# USBTINYISP.net
KiCad netlist of a schematic drawn in EAGLE
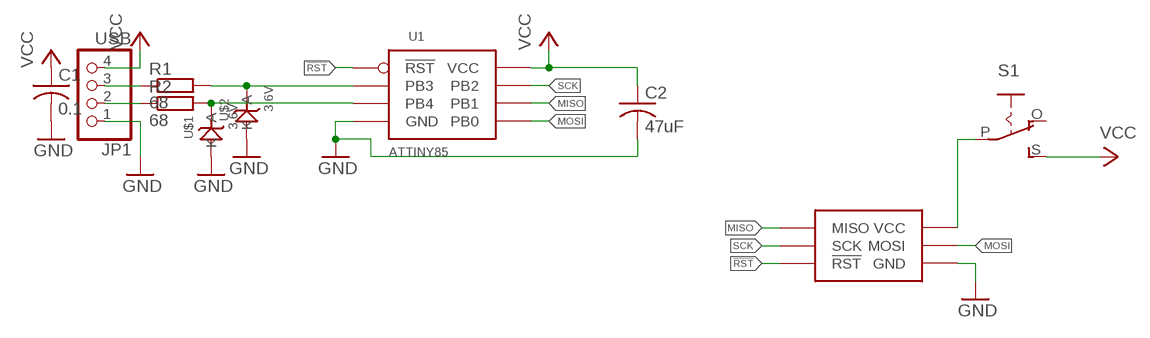
[diagram p0: schematic, sheet 1]

(export (version "E")
  (design (tool "Eeschema 10.0.6"))
  (components
    (comp (ref "C1")
      (value "0.1")
      (footprint "eagle-import:C025-025X050")
      (libsource (lib "eagle-import") (part "C-US025-025X050"))
    )
    (comp (ref "C2")
      (value "47uF")
      (footprint "eagle-import:C025-025X050")
      (libsource (lib "eagle-import") (part "C-US025-025X050"))
    )
    (comp (ref "ICSP1")
      (value "AVRISCP")
      (footprint "eagle-import:AVRICSP")
      (libsource (lib "eagle-import") (part "AVRISCP"))
    )
    (comp (ref "JP1")
      (value "USB")
      (footprint "eagle-import:1X04")
      (libsource (lib "eagle-import") (part "PINHD-1X4"))
    )
    (comp (ref "R1")
      (value "68")
      (footprint "eagle-import:0207_7")
      (libsource (lib "eagle-import") (part "R-EU_0207/7"))
    )
    (comp (ref "R2")
      (value "68")
      (footprint "eagle-import:0207_7")
      (libsource (lib "eagle-import") (part "R-EU_0207/7"))
    )
    (comp (ref "S1")
      (value "EG1218S")
      (footprint "eagle-import:EG1218")
      (libsource (lib "eagle-import") (part "EG1218S"))
    )
    (comp (ref "U$1")
      (value "3.6V")
      (footprint "eagle-import:Z3V6")
      (libsource (lib "eagle-import") (part "Z3V6"))
    )
    (comp (ref "U$2")
      (value "3.6V")
      (footprint "eagle-import:Z3V6")
      (libsource (lib "eagle-import") (part "Z3V6"))
    )
    (comp (ref "U1")
      (value "ATTINY85")
      (footprint "eagle-import:DIP8")
      (libsource (lib "eagle-import") (part "ATTINY85"))
    )
  )
  (nets
    (net (code "1") (name "/~{RST}") (class "Default")
      (node (ref "ICSP1") (pin "P$5") (pinfunction "~{RST}_P$5") (pintype "bidirectional"))
      (node (ref "U1") (pin "P$1") (pinfunction "~{RST}_P$1") (pintype "bidirectional"))
    )
    (net (code "2") (name "GND") (class "Default")
      (node (ref "C1") (pin "2") (pinfunction "2_2") (pintype "passive"))
      (node (ref "C2") (pin "2") (pinfunction "2_2") (pintype "passive"))
      (node (ref "ICSP1") (pin "P$6") (pinfunction "GND_P$6") (pintype "power_in"))
      (node (ref "JP1") (pin "1") (pinfunction "1_1") (pintype "passive"))
      (node (ref "U$1") (pin "P$2") (pinfunction "A_P$2") (pintype "power_in"))
      (node (ref "U$2") (pin "P$2") (pinfunction "A_P$2") (pintype "power_in"))
      (node (ref "U1") (pin "P$4") (pinfunction "GND_P$4") (pintype "power_in"))
    )
    (net (code "3") (name "MISO") (class "Default")
      (node (ref "ICSP1") (pin "P$1") (pinfunction "MISO_P$1") (pintype "bidirectional"))
      (node (ref "U1") (pin "P$6") (pinfunction "PB1_P$6") (pintype "bidirectional"))
    )
    (net (code "4") (name "MOSI") (class "Default")
      (node (ref "ICSP1") (pin "P$4") (pinfunction "MOSI_P$4") (pintype "bidirectional"))
      (node (ref "U1") (pin "P$5") (pinfunction "PB0_P$5") (pintype "bidirectional"))
    )
    (net (code "5") (name "Net-(ICSP1-VCC)") (class "Default")
      (node (ref "ICSP1") (pin "P$2") (pinfunction "VCC_P$2") (pintype "power_in"))
      (node (ref "S1") (pin "P") (pinfunction "P_P") (pintype "passive"))
    )
    (net (code "6") (name "Net-(JP1-Pad2)") (class "Default")
      (node (ref "JP1") (pin "2") (pinfunction "2_2") (pintype "passive"))
      (node (ref "R2") (pin "1") (pinfunction "1_1") (pintype "passive"))
    )
    (net (code "7") (name "Net-(JP1-Pad3)") (class "Default")
      (node (ref "JP1") (pin "3") (pinfunction "3_3") (pintype "passive"))
      (node (ref "R1") (pin "1") (pinfunction "1_1") (pintype "passive"))
    )
    (net (code "8") (name "Net-(U$1-K)") (class "Default")
      (node (ref "R2") (pin "2") (pinfunction "2_2") (pintype "passive"))
      (node (ref "U$1") (pin "P$1") (pinfunction "K_P$1") (pintype "power_in"))
      (node (ref "U1") (pin "P$3") (pinfunction "PB4_P$3") (pintype "bidirectional"))
    )
    (net (code "9") (name "Net-(U$2-K)") (class "Default")
      (node (ref "R1") (pin "2") (pinfunction "2_2") (pintype "passive"))
      (node (ref "U$2") (pin "P$1") (pinfunction "K_P$1") (pintype "power_in"))
      (node (ref "U1") (pin "P$2") (pinfunction "PB3_P$2") (pintype "bidirectional"))
    )
    (net (code "10") (name "SCK") (class "Default")
      (node (ref "ICSP1") (pin "P$3") (pinfunction "SCK_P$3") (pintype "bidirectional"))
      (node (ref "U1") (pin "P$7") (pinfunction "PB2_P$7") (pintype "bidirectional"))
    )
    (net (code "11") (name "VCC") (class "Default")
      (node (ref "C1") (pin "1") (pinfunction "1_1") (pintype "passive"))
      (node (ref "C2") (pin "1") (pinfunction "1_1") (pintype "passive"))
      (node (ref "JP1") (pin "4") (pinfunction "4_4") (pintype "passive"))
      (node (ref "S1") (pin "S") (pinfunction "S_S") (pintype "passive"))
      (node (ref "U1") (pin "P$8") (pinfunction "VCC_P$8") (pintype "power_in"))
    )
    (net (code "12") (name "unconnected-(S1-PadO)") (class "Default")
      (node (ref "S1") (pin "O") (pinfunction "O_O") (pintype "passive"))
    )
  )
)
